# proto.net
KiCad netlist of a schematic drawn in EAGLE
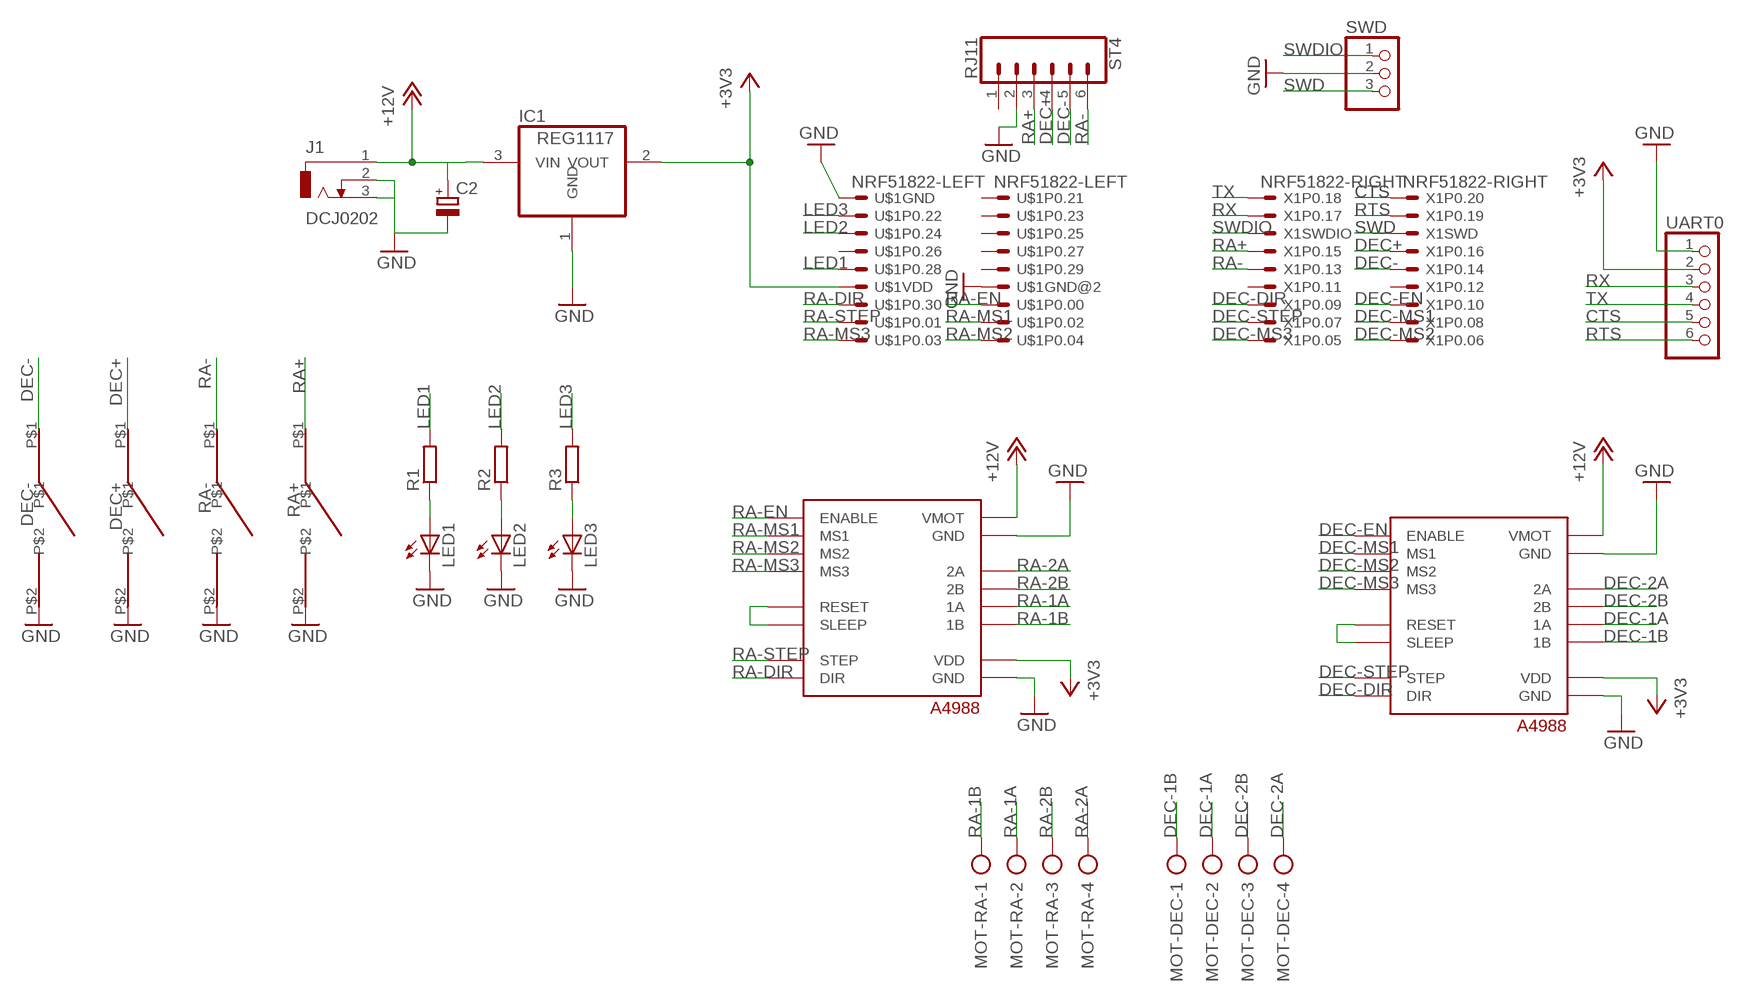
[diagram p0: schematic, sheet 1]

(export (version "E")
  (design (tool "Eeschema 10.0.6"))
  (components
    (comp (ref "C2")
      (value "CPOL-EUSMCC")
      (footprint "eagle-import:SMC_C")
      (libsource (lib "eagle-import") (part "CPOL-EUSMCC"))
    )
    (comp (ref "DEC+")
      (value "TACT-SWITCH")
      (footprint "eagle-import:TACT-SWITCH-THT")
      (libsource (lib "eagle-import") (part "TACT-SWITCH"))
    )
    (comp (ref "DEC-")
      (value "TACT-SWITCH")
      (footprint "eagle-import:TACT-SWITCH-THT")
      (libsource (lib "eagle-import") (part "TACT-SWITCH"))
    )
    (comp (ref "DRV-DEC")
      (value "A4988_ALL")
      (footprint "eagle-import:A4988_ALL")
      (libsource (lib "eagle-import") (part "A4988_ALL"))
    )
    (comp (ref "DRV-RA")
      (value "A4988_ALL")
      (footprint "eagle-import:A4988_ALL")
      (libsource (lib "eagle-import") (part "A4988_ALL"))
    )
    (comp (ref "IC1")
      (value "REG1117")
      (footprint "eagle-import:SOT223")
      (libsource (lib "eagle-import") (part "REG1117"))
    )
    (comp (ref "J1")
      (value "DCJ0202")
      (footprint "eagle-import:DCJ0202")
      (libsource (lib "eagle-import") (part "DCJ0202"))
    )
    (comp (ref "LED1")
      (value "LEDSML1206")
      (footprint "eagle-import:SML1206")
      (libsource (lib "eagle-import") (part "LEDSML1206"))
    )
    (comp (ref "LED2")
      (value "LEDSML1206")
      (footprint "eagle-import:SML1206")
      (libsource (lib "eagle-import") (part "LEDSML1206"))
    )
    (comp (ref "LED3")
      (value "LEDSML1206")
      (footprint "eagle-import:SML1206")
      (libsource (lib "eagle-import") (part "LEDSML1206"))
    )
    (comp (ref "MOT-DEC")
      (value "AK500/4")
      (footprint "eagle-import:AK500_4")
      (libsource (lib "eagle-import") (part "AK500/4"))
    )
    (comp (ref "MOT-RA")
      (value "AK500/4")
      (footprint "eagle-import:AK500_4")
      (libsource (lib "eagle-import") (part "AK500/4"))
    )
    (comp (ref "R1")
      (value "RR1206")
      (footprint "eagle-import:R1206")
      (libsource (lib "eagle-import") (part "RR1206"))
    )
    (comp (ref "R2")
      (value "RR1206")
      (footprint "eagle-import:R1206")
      (libsource (lib "eagle-import") (part "RR1206"))
    )
    (comp (ref "R3")
      (value "RR1206")
      (footprint "eagle-import:R1206")
      (libsource (lib "eagle-import") (part "RR1206"))
    )
    (comp (ref "RA+")
      (value "TACT-SWITCH")
      (footprint "eagle-import:TACT-SWITCH-THT")
      (libsource (lib "eagle-import") (part "TACT-SWITCH"))
    )
    (comp (ref "RA-")
      (value "TACT-SWITCH")
      (footprint "eagle-import:TACT-SWITCH-THT")
      (libsource (lib "eagle-import") (part "TACT-SWITCH"))
    )
    (comp (ref "ST4")
      (value "RJ11")
      (footprint "eagle-import:RJ11-6")
      (libsource (lib "eagle-import") (part "RJ11-6"))
    )
    (comp (ref "SWD")
      (value "PINHD-1X3")
      (footprint "eagle-import:1X03")
      (libsource (lib "eagle-import") (part "PINHD-1X3"))
    )
    (comp (ref "U$1")
      (value "NRF51822-LEFT")
      (footprint "eagle-import:NRF51822-LEFT")
      (fields (field (name "MPN") "NRF51822-left"))
      (libsource (lib "eagle-import") (part "NRF51822-LEFT"))
    )
    (comp (ref "UART0")
      (value "PINHD-1X6")
      (footprint "eagle-import:1X06")
      (libsource (lib "eagle-import") (part "PINHD-1X6"))
    )
    (comp (ref "X1")
      (value "NRF51822-RIGHT")
      (footprint "eagle-import:NRF51822-RIGHT")
      (fields (field (name "MPN") "NRF51822-right"))
      (libsource (lib "eagle-import") (part "NRF51822-RIGHT"))
    )
  )
  (nets
    (net (code "1") (name "+3V3") (class "Default")
      (node (ref "DRV-DEC") (pin "P15") (pinfunction "VDD_P15") (pintype "bidirectional"))
      (node (ref "DRV-RA") (pin "P15") (pinfunction "VDD_P15") (pintype "bidirectional"))
      (node (ref "IC1") (pin "2") (pinfunction "VOUT_2") (pintype "output"))
      (node (ref "U$1") (pin "11") (pinfunction "S_11") (pintype "passive"))
      (node (ref "UART0") (pin "2") (pinfunction "2_2") (pintype "passive"))
    )
    (net (code "2") (name "+12V") (class "Default")
      (node (ref "C2") (pin "+") (pinfunction "+_+") (pintype "passive"))
      (node (ref "DRV-DEC") (pin "P9") (pinfunction "VMOT_P9") (pintype "bidirectional"))
      (node (ref "DRV-RA") (pin "P9") (pinfunction "VMOT_P9") (pintype "bidirectional"))
      (node (ref "IC1") (pin "3") (pinfunction "VIN_3") (pintype "input"))
      (node (ref "J1") (pin "1") (pinfunction "1_1") (pintype "passive"))
    )
    (net (code "3") (name "/CTS") (class "Default")
      (node (ref "UART0") (pin "5") (pinfunction "5_5") (pintype "passive"))
      (node (ref "X1") (pin "2") (pinfunction "S_2") (pintype "passive"))
    )
    (net (code "4") (name "/DEC+") (class "Default")
      (node (ref "DEC+") (pin "P$1") (pinfunction "P$1_P$1") (pintype "bidirectional"))
      (node (ref "ST4") (pin "4") (pinfunction "4_4") (pintype "passive"))
      (node (ref "X1") (pin "8") (pinfunction "S_8") (pintype "passive"))
    )
    (net (code "5") (name "/DEC-") (class "Default")
      (node (ref "DEC-") (pin "P$1") (pinfunction "P$1_P$1") (pintype "bidirectional"))
      (node (ref "ST4") (pin "5") (pinfunction "5_5") (pintype "passive"))
      (node (ref "X1") (pin "10") (pinfunction "S_10") (pintype "passive"))
    )
    (net (code "6") (name "/DEC-1A") (class "Default")
      (node (ref "DRV-DEC") (pin "P13") (pinfunction "1A_P13") (pintype "bidirectional"))
      (node (ref "MOT-DEC") (pin "2") (pinfunction "KL_2") (pintype "passive"))
    )
    (net (code "7") (name "/DEC-1B") (class "Default")
      (node (ref "DRV-DEC") (pin "P14") (pinfunction "1B_P14") (pintype "bidirectional"))
      (node (ref "MOT-DEC") (pin "1") (pinfunction "KL_1") (pintype "passive"))
    )
    (net (code "8") (name "/DEC-2A") (class "Default")
      (node (ref "DRV-DEC") (pin "P11") (pinfunction "2A_P11") (pintype "bidirectional"))
      (node (ref "MOT-DEC") (pin "4") (pinfunction "KL_4") (pintype "passive"))
    )
    (net (code "9") (name "/DEC-2B") (class "Default")
      (node (ref "DRV-DEC") (pin "P12") (pinfunction "2B_P12") (pintype "bidirectional"))
      (node (ref "MOT-DEC") (pin "3") (pinfunction "KL_3") (pintype "passive"))
    )
    (net (code "10") (name "/DEC-DIR") (class "Default")
      (node (ref "DRV-DEC") (pin "P8") (pinfunction "DIR_P8") (pintype "bidirectional"))
      (node (ref "X1") (pin "13") (pinfunction "S_13") (pintype "passive"))
    )
    (net (code "11") (name "/DEC-EN") (class "Default")
      (node (ref "DRV-DEC") (pin "P1") (pinfunction "ENABLE_P1") (pintype "bidirectional"))
      (node (ref "X1") (pin "14") (pinfunction "S_14") (pintype "passive"))
    )
    (net (code "12") (name "/DEC-MS1") (class "Default")
      (node (ref "DRV-DEC") (pin "P2") (pinfunction "MS1_P2") (pintype "bidirectional"))
      (node (ref "X1") (pin "16") (pinfunction "S_16") (pintype "passive"))
    )
    (net (code "13") (name "/DEC-MS2") (class "Default")
      (node (ref "DRV-DEC") (pin "P3") (pinfunction "MS2_P3") (pintype "bidirectional"))
      (node (ref "X1") (pin "18") (pinfunction "S_18") (pintype "passive"))
    )
    (net (code "14") (name "/DEC-MS3") (class "Default")
      (node (ref "DRV-DEC") (pin "P4") (pinfunction "MS3_P4") (pintype "bidirectional"))
      (node (ref "X1") (pin "17") (pinfunction "S_17") (pintype "passive"))
    )
    (net (code "15") (name "/DEC-STEP") (class "Default")
      (node (ref "DRV-DEC") (pin "P7") (pinfunction "STEP_P7") (pintype "bidirectional"))
      (node (ref "X1") (pin "15") (pinfunction "S_15") (pintype "passive"))
    )
    (net (code "16") (name "/LED1") (class "Default")
      (node (ref "R1") (pin "2") (pinfunction "2_2") (pintype "passive"))
      (node (ref "U$1") (pin "9") (pinfunction "S_9") (pintype "passive"))
    )
    (net (code "17") (name "/LED2") (class "Default")
      (node (ref "R2") (pin "2") (pinfunction "2_2") (pintype "passive"))
      (node (ref "U$1") (pin "5") (pinfunction "S_5") (pintype "passive"))
    )
    (net (code "18") (name "/LED3") (class "Default")
      (node (ref "R3") (pin "2") (pinfunction "2_2") (pintype "passive"))
      (node (ref "U$1") (pin "3") (pinfunction "S_3") (pintype "passive"))
    )
    (net (code "19") (name "/RA+") (class "Default")
      (node (ref "RA+") (pin "P$1") (pinfunction "P$1_P$1") (pintype "bidirectional"))
      (node (ref "ST4") (pin "3") (pinfunction "3_3") (pintype "passive"))
      (node (ref "X1") (pin "7") (pinfunction "S_7") (pintype "passive"))
    )
    (net (code "20") (name "/RA-") (class "Default")
      (node (ref "RA-") (pin "P$1") (pinfunction "P$1_P$1") (pintype "bidirectional"))
      (node (ref "ST4") (pin "6") (pinfunction "6_6") (pintype "passive"))
      (node (ref "X1") (pin "9") (pinfunction "S_9") (pintype "passive"))
    )
    (net (code "21") (name "/RA-1A") (class "Default")
      (node (ref "DRV-RA") (pin "P13") (pinfunction "1A_P13") (pintype "bidirectional"))
      (node (ref "MOT-RA") (pin "2") (pinfunction "KL_2") (pintype "passive"))
    )
    (net (code "22") (name "/RA-1B") (class "Default")
      (node (ref "DRV-RA") (pin "P14") (pinfunction "1B_P14") (pintype "bidirectional"))
      (node (ref "MOT-RA") (pin "1") (pinfunction "KL_1") (pintype "passive"))
    )
    (net (code "23") (name "/RA-2A") (class "Default")
      (node (ref "DRV-RA") (pin "P11") (pinfunction "2A_P11") (pintype "bidirectional"))
      (node (ref "MOT-RA") (pin "4") (pinfunction "KL_4") (pintype "passive"))
    )
    (net (code "24") (name "/RA-2B") (class "Default")
      (node (ref "DRV-RA") (pin "P12") (pinfunction "2B_P12") (pintype "bidirectional"))
      (node (ref "MOT-RA") (pin "3") (pinfunction "KL_3") (pintype "passive"))
    )
    (net (code "25") (name "/RA-DIR") (class "Default")
      (node (ref "DRV-RA") (pin "P8") (pinfunction "DIR_P8") (pintype "bidirectional"))
      (node (ref "U$1") (pin "13") (pinfunction "S_13") (pintype "passive"))
    )
    (net (code "26") (name "/RA-EN") (class "Default")
      (node (ref "DRV-RA") (pin "P1") (pinfunction "ENABLE_P1") (pintype "bidirectional"))
      (node (ref "U$1") (pin "14") (pinfunction "S_14") (pintype "passive"))
    )
    (net (code "27") (name "/RA-MS1") (class "Default")
      (node (ref "DRV-RA") (pin "P2") (pinfunction "MS1_P2") (pintype "bidirectional"))
      (node (ref "U$1") (pin "16") (pinfunction "S_16") (pintype "passive"))
    )
    (net (code "28") (name "/RA-MS2") (class "Default")
      (node (ref "DRV-RA") (pin "P3") (pinfunction "MS2_P3") (pintype "bidirectional"))
      (node (ref "U$1") (pin "18") (pinfunction "S_18") (pintype "passive"))
    )
    (net (code "29") (name "/RA-MS3") (class "Default")
      (node (ref "DRV-RA") (pin "P4") (pinfunction "MS3_P4") (pintype "bidirectional"))
      (node (ref "U$1") (pin "17") (pinfunction "S_17") (pintype "passive"))
    )
    (net (code "30") (name "/RA-STEP") (class "Default")
      (node (ref "DRV-RA") (pin "P7") (pinfunction "STEP_P7") (pintype "bidirectional"))
      (node (ref "U$1") (pin "15") (pinfunction "S_15") (pintype "passive"))
    )
    (net (code "31") (name "/RTS") (class "Default")
      (node (ref "UART0") (pin "6") (pinfunction "6_6") (pintype "passive"))
      (node (ref "X1") (pin "4") (pinfunction "S_4") (pintype "passive"))
    )
    (net (code "32") (name "/RX") (class "Default")
      (node (ref "UART0") (pin "3") (pinfunction "3_3") (pintype "passive"))
      (node (ref "X1") (pin "3") (pinfunction "S_3") (pintype "passive"))
    )
    (net (code "33") (name "/SWD") (class "Default")
      (node (ref "SWD") (pin "3") (pinfunction "3_3") (pintype "passive"))
      (node (ref "X1") (pin "6") (pinfunction "S_6") (pintype "passive"))
    )
    (net (code "34") (name "/SWDIO") (class "Default")
      (node (ref "SWD") (pin "1") (pinfunction "1_1") (pintype "passive"))
      (node (ref "X1") (pin "5") (pinfunction "S_5") (pintype "passive"))
    )
    (net (code "35") (name "/TX") (class "Default")
      (node (ref "UART0") (pin "4") (pinfunction "4_4") (pintype "passive"))
      (node (ref "X1") (pin "1") (pinfunction "S_1") (pintype "passive"))
    )
    (net (code "36") (name "GND") (class "Default")
      (node (ref "C2") (pin "-") (pinfunction "-_-") (pintype "passive"))
      (node (ref "DEC+") (pin "P$2") (pinfunction "P$2_P$2") (pintype "bidirectional"))
      (node (ref "DEC-") (pin "P$2") (pinfunction "P$2_P$2") (pintype "bidirectional"))
      (node (ref "DRV-DEC") (pin "P10") (pinfunction "GND_P10") (pintype "bidirectional"))
      (node (ref "DRV-DEC") (pin "P16") (pinfunction "GND_P16") (pintype "bidirectional"))
      (node (ref "DRV-RA") (pin "P10") (pinfunction "GND_P10") (pintype "bidirectional"))
      (node (ref "DRV-RA") (pin "P16") (pinfunction "GND_P16") (pintype "bidirectional"))
      (node (ref "IC1") (pin "1") (pinfunction "GND_1") (pintype "power_in"))
      (node (ref "J1") (pin "2") (pinfunction "2_2") (pintype "passive"))
      (node (ref "J1") (pin "3") (pinfunction "3_3") (pintype "passive"))
      (node (ref "LED1") (pin "C") (pinfunction "C_C") (pintype "passive"))
      (node (ref "LED2") (pin "C") (pinfunction "C_C") (pintype "passive"))
      (node (ref "LED3") (pin "C") (pinfunction "C_C") (pintype "passive"))
      (node (ref "RA+") (pin "P$2") (pinfunction "P$2_P$2") (pintype "bidirectional"))
      (node (ref "RA-") (pin "P$2") (pinfunction "P$2_P$2") (pintype "bidirectional"))
      (node (ref "ST4") (pin "2") (pinfunction "2_2") (pintype "passive"))
      (node (ref "SWD") (pin "2") (pinfunction "2_2") (pintype "passive"))
      (node (ref "U$1") (pin "1") (pinfunction "S_1") (pintype "passive"))
      (node (ref "U$1") (pin "12") (pinfunction "S_12") (pintype "passive"))
      (node (ref "UART0") (pin "1") (pinfunction "1_1") (pintype "passive"))
    )
    (net (code "37") (name "Net-(DRV-DEC-RESET)") (class "Default")
      (node (ref "DRV-DEC") (pin "P5") (pinfunction "RESET_P5") (pintype "bidirectional"))
      (node (ref "DRV-DEC") (pin "P6") (pinfunction "SLEEP_P6") (pintype "bidirectional"))
    )
    (net (code "38") (name "Net-(DRV-RA-RESET)") (class "Default")
      (node (ref "DRV-RA") (pin "P5") (pinfunction "RESET_P5") (pintype "bidirectional"))
      (node (ref "DRV-RA") (pin "P6") (pinfunction "SLEEP_P6") (pintype "bidirectional"))
    )
    (net (code "39") (name "Net-(LED1-PadA)") (class "Default")
      (node (ref "LED1") (pin "A") (pinfunction "A_A") (pintype "passive"))
      (node (ref "R1") (pin "1") (pinfunction "1_1") (pintype "passive"))
    )
    (net (code "40") (name "Net-(LED2-PadA)") (class "Default")
      (node (ref "LED2") (pin "A") (pinfunction "A_A") (pintype "passive"))
      (node (ref "R2") (pin "1") (pinfunction "1_1") (pintype "passive"))
    )
    (net (code "41") (name "Net-(LED3-PadA)") (class "Default")
      (node (ref "LED3") (pin "A") (pinfunction "A_A") (pintype "passive"))
      (node (ref "R3") (pin "1") (pinfunction "1_1") (pintype "passive"))
    )
    (net (code "42") (name "unconnected-(ST4-Pad1)") (class "Default")
      (node (ref "ST4") (pin "1") (pinfunction "1_1") (pintype "passive"))
    )
    (net (code "43") (name "unconnected-(U$1H-S-Pad2)") (class "Default")
      (node (ref "U$1") (pin "2") (pinfunction "S_2") (pintype "passive"))
    )
    (net (code "44") (name "unconnected-(U$1J-S-Pad4)") (class "Default")
      (node (ref "U$1") (pin "4") (pinfunction "S_4") (pintype "passive"))
    )
    (net (code "45") (name "unconnected-(U$1L-S-Pad6)") (class "Default")
      (node (ref "U$1") (pin "6") (pinfunction "S_6") (pintype "passive"))
    )
    (net (code "46") (name "unconnected-(U$1M-S-Pad7)") (class "Default")
      (node (ref "U$1") (pin "7") (pinfunction "S_7") (pintype "passive"))
    )
    (net (code "47") (name "unconnected-(U$1N-S-Pad8)") (class "Default")
      (node (ref "U$1") (pin "8") (pinfunction "S_8") (pintype "passive"))
    )
    (net (code "48") (name "unconnected-(U$1P-S-Pad10)") (class "Default")
      (node (ref "U$1") (pin "10") (pinfunction "S_10") (pintype "passive"))
    )
    (net (code "49") (name "unconnected-(X1G-S-Pad11)") (class "Default")
      (node (ref "X1") (pin "11") (pinfunction "S_11") (pintype "passive"))
    )
    (net (code "50") (name "unconnected-(X1H-S-Pad12)") (class "Default")
      (node (ref "X1") (pin "12") (pinfunction "S_12") (pintype "passive"))
    )
  )
)
